# ESP32S2_STICK.net
KiCad netlist of a schematic drawn in EAGLE
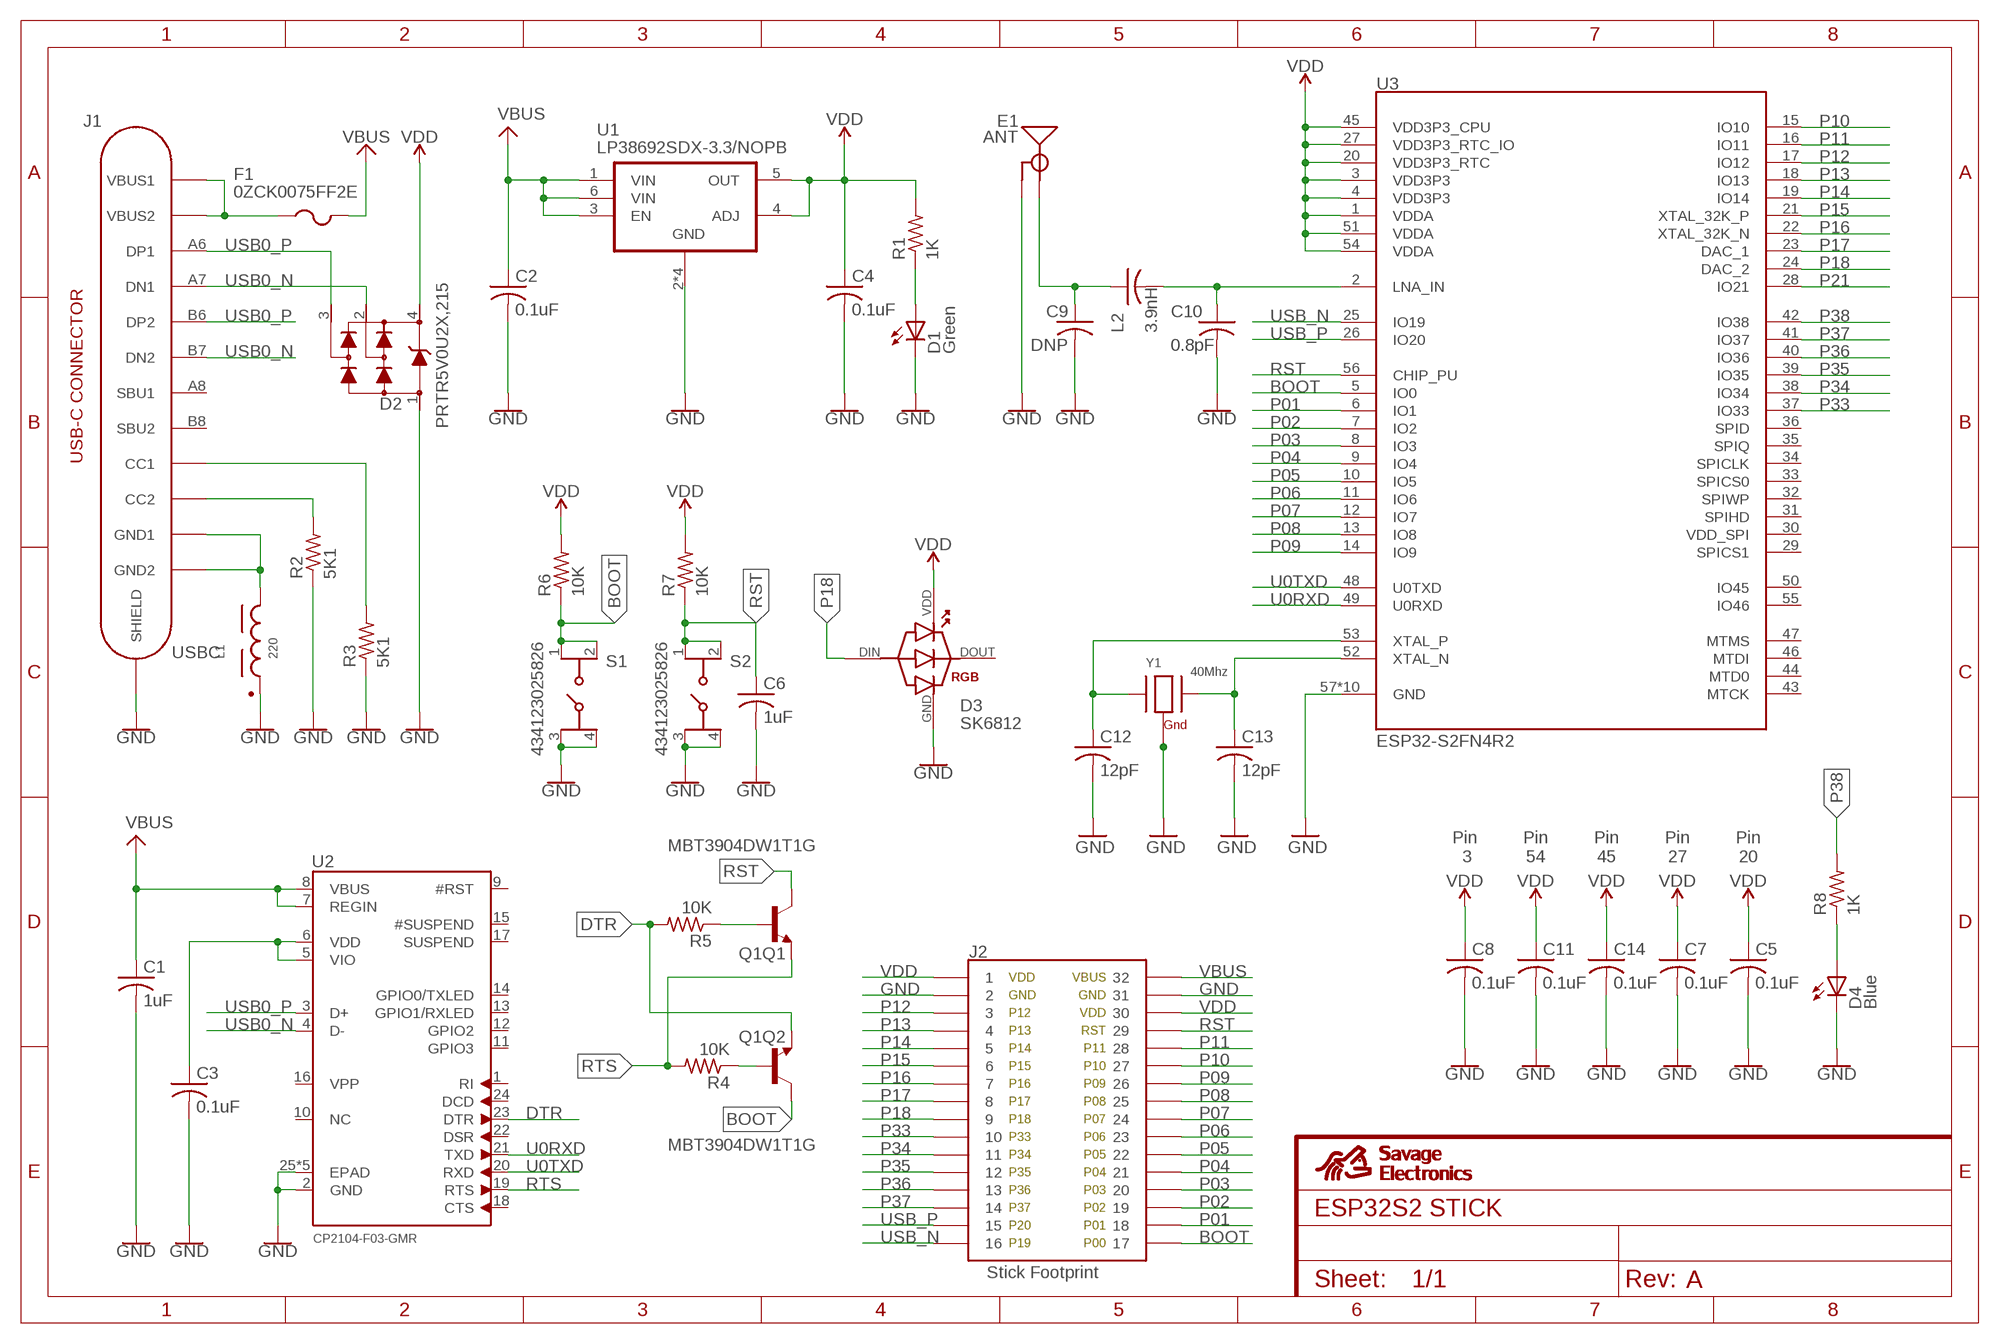
[diagram p0: schematic, sheet 1]

(export (version "E")
  (design (tool "Eeschema 10.0.6"))
  (components
    (comp (ref "C1")
      (value "1uF")
      (footprint "eagle-import:C0603")
      (libsource (lib "eagle-import") (part "adafruit_8559999_C-USC0603"))
    )
    (comp (ref "C2")
      (value "0.1uF")
      (footprint "eagle-import:C0603")
      (libsource (lib "eagle-import") (part "C-USC0603"))
    )
    (comp (ref "C3")
      (value "0.1uF")
      (footprint "eagle-import:C0603")
      (libsource (lib "eagle-import") (part "C-USC0603"))
    )
    (comp (ref "C4")
      (value "0.1uF")
      (footprint "eagle-import:C0603")
      (libsource (lib "eagle-import") (part "C-USC0603"))
    )
    (comp (ref "C5")
      (value "0.1uF")
      (footprint "eagle-import:C0603")
      (libsource (lib "eagle-import") (part "C-USC0603"))
    )
    (comp (ref "C6")
      (value "1uF")
      (footprint "eagle-import:C0603")
      (libsource (lib "eagle-import") (part "C-USC0603"))
    )
    (comp (ref "C7")
      (value "0.1uF")
      (footprint "eagle-import:C0603")
      (libsource (lib "eagle-import") (part "C-USC0603"))
    )
    (comp (ref "C8")
      (value "0.1uF")
      (footprint "eagle-import:C0603")
      (libsource (lib "eagle-import") (part "C-USC0603"))
    )
    (comp (ref "C9")
      (value "DNP")
      (footprint "eagle-import:C0402")
      (libsource (lib "eagle-import") (part "C-USC0402"))
    )
    (comp (ref "C10")
      (value "0.8pF")
      (footprint "eagle-import:C0402")
      (libsource (lib "eagle-import") (part "C-USC0402"))
    )
    (comp (ref "C11")
      (value "0.1uF")
      (footprint "eagle-import:C0603")
      (libsource (lib "eagle-import") (part "C-USC0603"))
    )
    (comp (ref "C12")
      (value "12pF")
      (footprint "eagle-import:C0402")
      (libsource (lib "eagle-import") (part "C-USC0402"))
    )
    (comp (ref "C13")
      (value "12pF")
      (footprint "eagle-import:C0402")
      (libsource (lib "eagle-import") (part "C-USC0402"))
    )
    (comp (ref "C14")
      (value "0.1uF")
      (footprint "eagle-import:C0603")
      (libsource (lib "eagle-import") (part "C-USC0603"))
    )
    (comp (ref "D1")
      (value "Green")
      (footprint "eagle-import:CHIP-LED0603")
      (libsource (lib "eagle-import") (part "LEDCHIP-LED0603"))
    )
    (comp (ref "D2")
      (value "PRTR5V0U2X,215")
      (footprint "eagle-import:SOT143B")
      (libsource (lib "eagle-import") (part "PRTR5V0U2X,215"))
    )
    (comp (ref "D3")
      (value "SK6812")
      (footprint "eagle-import:20X20")
      (libsource (lib "eagle-import") (part "SK6812"))
    )
    (comp (ref "D4")
      (value "Blue")
      (footprint "eagle-import:CHIP-LED0603")
      (libsource (lib "eagle-import") (part "LEDCHIP-LED0603"))
    )
    (comp (ref "E1")
      (value "ANT")
      (footprint "eagle-import:TRACE_ANTENNA_2.4GHZ_15.2MM")
      (libsource (lib "eagle-import") (part "ANTENNA-GROUNDEDTRACE-15.2MM"))
    )
    (comp (ref "F1")
      (value "0ZCK0075FF2E")
      (footprint "eagle-import:R0603F")
      (libsource (lib "eagle-import") (part "PTCFUSE"))
    )
    (comp (ref "J1")
      (value "USBC")
      (footprint "eagle-import:USBC")
      (libsource (lib "eagle-import") (part "USBC"))
    )
    (comp (ref "J2")
      (value "Stick Footprint")
      (footprint "eagle-import:NRF52832_CASTELLATED")
      (libsource (lib "eagle-import") (part "NRF52832PRO"))
    )
    (comp (ref "L1")
      (value "220")
      (footprint "eagle-import:WE-CBA_0603(W=2.2)")
      (libsource (lib "eagle-import") (part "WE-CBA_0603_WB/HS_782631182"))
    )
    (comp (ref "L2")
      (value "3.9nH")
      (footprint "eagle-import:C0402")
      (libsource (lib "eagle-import") (part "C-USC0402"))
    )
    (comp (ref "Q1")
      (value "MBT3904DW1T1G")
      (footprint "eagle-import:SC70-6")
      (libsource (lib "eagle-import") (part "TRANS_NPN_DUAL-MBT3904DW1T1"))
    )
    (comp (ref "R1")
      (value "1K")
      (footprint "eagle-import:R0402")
      (libsource (lib "eagle-import") (part "R-US_R0402"))
    )
    (comp (ref "R2")
      (value "5K1")
      (footprint "eagle-import:R0402")
      (libsource (lib "eagle-import") (part "R-US_R0402"))
    )
    (comp (ref "R3")
      (value "5K1")
      (footprint "eagle-import:R0402")
      (libsource (lib "eagle-import") (part "R-US_R0402"))
    )
    (comp (ref "R4")
      (value "10K")
      (footprint "eagle-import:R0402")
      (libsource (lib "eagle-import") (part "R-US_R0402"))
    )
    (comp (ref "R5")
      (value "10K")
      (footprint "eagle-import:R0402")
      (libsource (lib "eagle-import") (part "R-US_R0402"))
    )
    (comp (ref "R6")
      (value "10K")
      (footprint "eagle-import:R0402")
      (libsource (lib "eagle-import") (part "R-US_R0402"))
    )
    (comp (ref "R7")
      (value "10K")
      (footprint "eagle-import:R0402")
      (libsource (lib "eagle-import") (part "R-US_R0402"))
    )
    (comp (ref "R8")
      (value "1K")
      (footprint "eagle-import:R0402")
      (libsource (lib "eagle-import") (part "R-US_R0402"))
    )
    (comp (ref "S1")
      (value "434123025826")
      (footprint "eagle-import:434123025826")
      (libsource (lib "eagle-import") (part "434123025826"))
    )
    (comp (ref "S2")
      (value "434123025826")
      (footprint "eagle-import:434123025826")
      (libsource (lib "eagle-import") (part "434123025826"))
    )
    (comp (ref "U1")
      (value "LP38692SDX-3.3/NOPB")
      (footprint "eagle-import:LLP6-3X3")
      (fields (field (name "MF") "Texas Instruments"))
      (libsource (lib "eagle-import") (part "LP38692SDX-3.3/NOPB"))
    )
    (comp (ref "U2")
      (value "CP2102N-A02-GQFN24R")
      (footprint "eagle-import:QFN24_4MM_SMSC")
      (libsource (lib "eagle-import") (part "CP2104"))
    )
    (comp (ref "U3")
      (value "ESP32-S2FN4R2")
      (footprint "eagle-import:QFN40P700X700X90-57T400N")
      (libsource (lib "eagle-import") (part "ESP32-S2QFN54"))
    )
    (comp (ref "Y1")
      (value "40Mhz")
      (footprint "eagle-import:NX2016")
      (libsource (lib "eagle-import") (part "XTAL-4"))
    )
  )
  (nets
    (net (code "1") (name "/P01") (class "Default")
      (node (ref "J2") (pin "16") (pinfunction "18_16") (pintype "bidirectional"))
      (node (ref "J2") (pin "16B") (pinfunction "18_16B") (pintype "bidirectional"))
      (node (ref "J2") (pin "16C") (pinfunction "18_16C") (pintype "bidirectional"))
      (node (ref "J2") (pin "P16") (pinfunction "18_P16") (pintype "bidirectional"))
      (node (ref "U3") (pin "6") (pinfunction "IO1_6") (pintype "bidirectional"))
    )
    (net (code "2") (name "/P02") (class "Default")
      (node (ref "J2") (pin "17") (pinfunction "19_17") (pintype "bidirectional"))
      (node (ref "J2") (pin "17B") (pinfunction "19_17B") (pintype "bidirectional"))
      (node (ref "J2") (pin "17C") (pinfunction "19_17C") (pintype "bidirectional"))
      (node (ref "J2") (pin "P17") (pinfunction "19_P17") (pintype "bidirectional"))
      (node (ref "U3") (pin "7") (pinfunction "IO2_7") (pintype "bidirectional"))
    )
    (net (code "3") (name "/P03") (class "Default")
      (node (ref "J2") (pin "18") (pinfunction "20_18") (pintype "bidirectional"))
      (node (ref "J2") (pin "18B") (pinfunction "20_18B") (pintype "bidirectional"))
      (node (ref "J2") (pin "18C") (pinfunction "20_18C") (pintype "bidirectional"))
      (node (ref "J2") (pin "P18") (pinfunction "20_P18") (pintype "bidirectional"))
      (node (ref "U3") (pin "8") (pinfunction "IO3_8") (pintype "bidirectional"))
    )
    (net (code "4") (name "/P04") (class "Default")
      (node (ref "J2") (pin "19") (pinfunction "21_19") (pintype "bidirectional"))
      (node (ref "J2") (pin "19B") (pinfunction "21_19B") (pintype "bidirectional"))
      (node (ref "J2") (pin "19C") (pinfunction "21_19C") (pintype "bidirectional"))
      (node (ref "J2") (pin "P19") (pinfunction "21_P19") (pintype "bidirectional"))
      (node (ref "U3") (pin "9") (pinfunction "IO4_9") (pintype "bidirectional"))
    )
    (net (code "5") (name "/P05") (class "Default")
      (node (ref "J2") (pin "20") (pinfunction "22_20") (pintype "bidirectional"))
      (node (ref "J2") (pin "20B") (pinfunction "22_20B") (pintype "bidirectional"))
      (node (ref "J2") (pin "20C") (pinfunction "22_20C") (pintype "bidirectional"))
      (node (ref "J2") (pin "P20") (pinfunction "22_P20") (pintype "bidirectional"))
      (node (ref "U3") (pin "10") (pinfunction "IO5_10") (pintype "bidirectional"))
    )
    (net (code "6") (name "/P06") (class "Default")
      (node (ref "J2") (pin "21") (pinfunction "23_21") (pintype "bidirectional"))
      (node (ref "J2") (pin "21B") (pinfunction "23_21B") (pintype "bidirectional"))
      (node (ref "J2") (pin "21C") (pinfunction "23_21C") (pintype "bidirectional"))
      (node (ref "J2") (pin "P21") (pinfunction "23_P21") (pintype "bidirectional"))
      (node (ref "U3") (pin "11") (pinfunction "IO6_11") (pintype "bidirectional"))
    )
    (net (code "7") (name "/P07") (class "Default")
      (node (ref "J2") (pin "22") (pinfunction "24_22") (pintype "bidirectional"))
      (node (ref "J2") (pin "22B") (pinfunction "24_22B") (pintype "bidirectional"))
      (node (ref "J2") (pin "22C") (pinfunction "24_22C") (pintype "bidirectional"))
      (node (ref "J2") (pin "P22") (pinfunction "24_P22") (pintype "bidirectional"))
      (node (ref "U3") (pin "12") (pinfunction "IO7_12") (pintype "bidirectional"))
    )
    (net (code "8") (name "/P08") (class "Default")
      (node (ref "J2") (pin "23") (pinfunction "25_23") (pintype "bidirectional"))
      (node (ref "J2") (pin "23B") (pinfunction "25_23B") (pintype "bidirectional"))
      (node (ref "J2") (pin "23C") (pinfunction "25_23C") (pintype "bidirectional"))
      (node (ref "J2") (pin "P23") (pinfunction "25_P23") (pintype "bidirectional"))
      (node (ref "U3") (pin "13") (pinfunction "IO8_13") (pintype "bidirectional"))
    )
    (net (code "9") (name "/P09") (class "Default")
      (node (ref "J2") (pin "24") (pinfunction "26_24") (pintype "bidirectional"))
      (node (ref "J2") (pin "24B") (pinfunction "26_24B") (pintype "bidirectional"))
      (node (ref "J2") (pin "24C") (pinfunction "26_24C") (pintype "bidirectional"))
      (node (ref "J2") (pin "P24") (pinfunction "26_P24") (pintype "bidirectional"))
      (node (ref "U3") (pin "14") (pinfunction "IO9_14") (pintype "bidirectional"))
    )
    (net (code "10") (name "/P10") (class "Default")
      (node (ref "J2") (pin "25") (pinfunction "27_25") (pintype "bidirectional"))
      (node (ref "J2") (pin "25B") (pinfunction "27_25B") (pintype "bidirectional"))
      (node (ref "J2") (pin "25C") (pinfunction "27_25C") (pintype "bidirectional"))
      (node (ref "J2") (pin "P25") (pinfunction "27_P25") (pintype "bidirectional"))
      (node (ref "U3") (pin "15") (pinfunction "IO10_15") (pintype "bidirectional"))
    )
    (net (code "11") (name "/P11") (class "Default")
      (node (ref "J2") (pin "26") (pinfunction "28_26") (pintype "bidirectional"))
      (node (ref "J2") (pin "26B") (pinfunction "28_26B") (pintype "bidirectional"))
      (node (ref "J2") (pin "26C") (pinfunction "28_26C") (pintype "bidirectional"))
      (node (ref "J2") (pin "P26") (pinfunction "28_P26") (pintype "bidirectional"))
      (node (ref "U3") (pin "16") (pinfunction "IO11_16") (pintype "bidirectional"))
    )
    (net (code "12") (name "/P12") (class "Default")
      (node (ref "J2") (pin "3") (pinfunction "3_3") (pintype "bidirectional"))
      (node (ref "J2") (pin "3B") (pinfunction "3_3B") (pintype "bidirectional"))
      (node (ref "J2") (pin "3C") (pinfunction "3_3C") (pintype "bidirectional"))
      (node (ref "J2") (pin "P3") (pinfunction "3_P3") (pintype "bidirectional"))
      (node (ref "U3") (pin "17") (pinfunction "IO12_17") (pintype "bidirectional"))
    )
    (net (code "13") (name "/P13") (class "Default")
      (node (ref "J2") (pin "4") (pinfunction "4_4") (pintype "bidirectional"))
      (node (ref "J2") (pin "4B") (pinfunction "4_4B") (pintype "bidirectional"))
      (node (ref "J2") (pin "4C") (pinfunction "4_4C") (pintype "bidirectional"))
      (node (ref "J2") (pin "P4") (pinfunction "4_P4") (pintype "bidirectional"))
      (node (ref "U3") (pin "18") (pinfunction "IO13_18") (pintype "bidirectional"))
    )
    (net (code "14") (name "/P14") (class "Default")
      (node (ref "J2") (pin "5") (pinfunction "5_5") (pintype "bidirectional"))
      (node (ref "J2") (pin "5B") (pinfunction "5_5B") (pintype "bidirectional"))
      (node (ref "J2") (pin "5C") (pinfunction "5_5C") (pintype "bidirectional"))
      (node (ref "J2") (pin "P5") (pinfunction "5_P5") (pintype "bidirectional"))
      (node (ref "U3") (pin "19") (pinfunction "IO14_19") (pintype "bidirectional"))
    )
    (net (code "15") (name "/P15") (class "Default")
      (node (ref "J2") (pin "6") (pinfunction "6_6") (pintype "bidirectional"))
      (node (ref "J2") (pin "6B") (pinfunction "6_6B") (pintype "bidirectional"))
      (node (ref "J2") (pin "6C") (pinfunction "6_6C") (pintype "bidirectional"))
      (node (ref "J2") (pin "P6") (pinfunction "6_P6") (pintype "bidirectional"))
      (node (ref "U3") (pin "21") (pinfunction "XTAL_32K_P_21") (pintype "bidirectional"))
    )
    (net (code "16") (name "/P16") (class "Default")
      (node (ref "J2") (pin "7") (pinfunction "7_7") (pintype "bidirectional"))
      (node (ref "J2") (pin "7B") (pinfunction "7_7B") (pintype "bidirectional"))
      (node (ref "J2") (pin "7C") (pinfunction "7_7C") (pintype "bidirectional"))
      (node (ref "J2") (pin "P7") (pinfunction "7_P7") (pintype "bidirectional"))
      (node (ref "U3") (pin "22") (pinfunction "XTAL_32K_N_22") (pintype "bidirectional"))
    )
    (net (code "17") (name "/P17") (class "Default")
      (node (ref "J2") (pin "8") (pinfunction "8_8") (pintype "bidirectional"))
      (node (ref "J2") (pin "8B") (pinfunction "8_8B") (pintype "bidirectional"))
      (node (ref "J2") (pin "8C") (pinfunction "8_8C") (pintype "bidirectional"))
      (node (ref "J2") (pin "P8") (pinfunction "8_P8") (pintype "bidirectional"))
      (node (ref "U3") (pin "23") (pinfunction "DAC_1_23") (pintype "bidirectional"))
    )
    (net (code "18") (name "/P21") (class "Default")
      (node (ref "U3") (pin "28") (pinfunction "IO21_28") (pintype "bidirectional"))
    )
    (net (code "19") (name "/P33") (class "Default")
      (node (ref "J2") (pin "10") (pinfunction "10_10") (pintype "bidirectional"))
      (node (ref "J2") (pin "10B") (pinfunction "10_10B") (pintype "bidirectional"))
      (node (ref "J2") (pin "10C") (pinfunction "10_10C") (pintype "bidirectional"))
      (node (ref "J2") (pin "P10") (pinfunction "10_P10") (pintype "bidirectional"))
      (node (ref "U3") (pin "37") (pinfunction "IO33_37") (pintype "bidirectional"))
    )
    (net (code "20") (name "/P34") (class "Default")
      (node (ref "J2") (pin "11") (pinfunction "11_11") (pintype "bidirectional"))
      (node (ref "J2") (pin "11B") (pinfunction "11_11B") (pintype "bidirectional"))
      (node (ref "J2") (pin "11C") (pinfunction "11_11C") (pintype "bidirectional"))
      (node (ref "J2") (pin "P11") (pinfunction "11_P11") (pintype "bidirectional"))
      (node (ref "U3") (pin "38") (pinfunction "IO34_38") (pintype "bidirectional"))
    )
    (net (code "21") (name "/P35") (class "Default")
      (node (ref "J2") (pin "12") (pinfunction "12_12") (pintype "bidirectional"))
      (node (ref "J2") (pin "12B") (pinfunction "12_12B") (pintype "bidirectional"))
      (node (ref "J2") (pin "12C") (pinfunction "12_12C") (pintype "bidirectional"))
      (node (ref "J2") (pin "P12") (pinfunction "12_P12") (pintype "bidirectional"))
      (node (ref "U3") (pin "39") (pinfunction "IO35_39") (pintype "bidirectional"))
    )
    (net (code "22") (name "/P36") (class "Default")
      (node (ref "J2") (pin "13") (pinfunction "13_13") (pintype "bidirectional"))
      (node (ref "J2") (pin "13B") (pinfunction "13_13B") (pintype "bidirectional"))
      (node (ref "J2") (pin "13C") (pinfunction "13_13C") (pintype "bidirectional"))
      (node (ref "J2") (pin "P13") (pinfunction "13_P13") (pintype "bidirectional"))
      (node (ref "U3") (pin "40") (pinfunction "IO36_40") (pintype "bidirectional"))
    )
    (net (code "23") (name "/P37") (class "Default")
      (node (ref "J2") (pin "14") (pinfunction "14_14") (pintype "bidirectional"))
      (node (ref "J2") (pin "14B") (pinfunction "14_14B") (pintype "bidirectional"))
      (node (ref "J2") (pin "14C") (pinfunction "14_14C") (pintype "bidirectional"))
      (node (ref "J2") (pin "P14") (pinfunction "14_P14") (pintype "bidirectional"))
      (node (ref "U3") (pin "41") (pinfunction "IO37_41") (pintype "bidirectional"))
    )
    (net (code "24") (name "/U0RXD") (class "Default")
      (node (ref "U2") (pin "21") (pinfunction "TXD_21") (pintype "output"))
      (node (ref "U3") (pin "49") (pinfunction "U0RXD_49") (pintype "bidirectional"))
    )
    (net (code "25") (name "/U0TXD") (class "Default")
      (node (ref "U2") (pin "20") (pinfunction "RXD_20") (pintype "input"))
      (node (ref "U3") (pin "48") (pinfunction "U0TXD_48") (pintype "bidirectional"))
    )
    (net (code "26") (name "/USB0_N") (class "Default")
      (node (ref "D2") (pin "2") (pinfunction "P$2_2") (pintype "passive"))
      (node (ref "J1") (pin "A7") (pinfunction "DN1_A7") (pintype "bidirectional"))
      (node (ref "J1") (pin "B7") (pinfunction "DN2_B7") (pintype "bidirectional"))
      (node (ref "U2") (pin "4") (pinfunction "D-_4") (pintype "bidirectional"))
    )
    (net (code "27") (name "/USB0_P") (class "Default")
      (node (ref "D2") (pin "3") (pinfunction "P$3_3") (pintype "passive"))
      (node (ref "J1") (pin "A6") (pinfunction "DP1_A6") (pintype "bidirectional"))
      (node (ref "J1") (pin "B6") (pinfunction "DP2_B6") (pintype "bidirectional"))
      (node (ref "U2") (pin "3") (pinfunction "D+_3") (pintype "bidirectional"))
    )
    (net (code "28") (name "/USB_N") (class "Default")
      (node (ref "J2") (pin "16AA") (pinfunction "16_16AA") (pintype "bidirectional"))
      (node (ref "J2") (pin "16BB") (pinfunction "16_16BB") (pintype "bidirectional"))
      (node (ref "J2") (pin "16CC") (pinfunction "16_16CC") (pintype "bidirectional"))
      (node (ref "J2") (pin "P16A") (pinfunction "16_P16A") (pintype "bidirectional"))
      (node (ref "U3") (pin "25") (pinfunction "IO19_25") (pintype "bidirectional"))
    )
    (net (code "29") (name "/USB_P") (class "Default")
      (node (ref "J2") (pin "15") (pinfunction "15_15") (pintype "bidirectional"))
      (node (ref "J2") (pin "15B") (pinfunction "15_15B") (pintype "bidirectional"))
      (node (ref "J2") (pin "15C") (pinfunction "15_15C") (pintype "bidirectional"))
      (node (ref "J2") (pin "P15") (pinfunction "15_P15") (pintype "bidirectional"))
      (node (ref "U3") (pin "26") (pinfunction "IO20_26") (pintype "bidirectional"))
    )
    (net (code "30") (name "/VDD_SPI") (class "Default")
      (node (ref "U3") (pin "30") (pinfunction "VDD_SPI_30") (pintype "power_in"))
    )
    (net (code "31") (name "BOOT") (class "Default")
      (node (ref "J2") (pin "17AA") (pinfunction "17_17AA") (pintype "bidirectional"))
      (node (ref "J2") (pin "17BB") (pinfunction "17_17BB") (pintype "bidirectional"))
      (node (ref "J2") (pin "17CC") (pinfunction "17_17CC") (pintype "bidirectional"))
      (node (ref "J2") (pin "P17DD") (pinfunction "17_P17DD") (pintype "bidirectional"))
      (node (ref "Q1") (pin "6") (pinfunction "C_6") (pintype "passive"))
      (node (ref "R6") (pin "1") (pinfunction "1_1") (pintype "passive"))
      (node (ref "S1") (pin "1") (pinfunction "1_1") (pintype "passive"))
      (node (ref "S1") (pin "2") (pinfunction "2_2") (pintype "passive"))
      (node (ref "U3") (pin "5") (pinfunction "IO0_5") (pintype "bidirectional"))
    )
    (net (code "32") (name "DTR") (class "Default")
      (node (ref "Q1") (pin "1") (pinfunction "E_1") (pintype "passive"))
      (node (ref "R5") (pin "2") (pinfunction "2_2") (pintype "passive"))
      (node (ref "U2") (pin "23") (pinfunction "DTR_23") (pintype "output"))
    )
    (net (code "33") (name "GND") (class "Default")
      (node (ref "C1") (pin "2") (pinfunction "2_2") (pintype "passive"))
      (node (ref "C10") (pin "2") (pinfunction "2_2") (pintype "passive"))
      (node (ref "C11") (pin "2") (pinfunction "2_2") (pintype "passive"))
      (node (ref "C12") (pin "2") (pinfunction "2_2") (pintype "passive"))
      (node (ref "C13") (pin "2") (pinfunction "2_2") (pintype "passive"))
      (node (ref "C14") (pin "2") (pinfunction "2_2") (pintype "passive"))
      (node (ref "C2") (pin "2") (pinfunction "2_2") (pintype "passive"))
      (node (ref "C3") (pin "2") (pinfunction "2_2") (pintype "passive"))
      (node (ref "C4") (pin "2") (pinfunction "2_2") (pintype "passive"))
      (node (ref "C5") (pin "2") (pinfunction "2_2") (pintype "passive"))
      (node (ref "C6") (pin "2") (pinfunction "2_2") (pintype "passive"))
      (node (ref "C7") (pin "2") (pinfunction "2_2") (pintype "passive"))
      (node (ref "C8") (pin "2") (pinfunction "2_2") (pintype "passive"))
      (node (ref "C9") (pin "2") (pinfunction "2_2") (pintype "passive"))
      (node (ref "D1") (pin "C") (pinfunction "C_C") (pintype "passive"))
      (node (ref "D2") (pin "1") (pinfunction "P$1_1") (pintype "passive"))
      (node (ref "D3") (pin "3") (pinfunction "GND_3") (pintype "bidirectional"))
      (node (ref "D4") (pin "C") (pinfunction "C_C") (pintype "passive"))
      (node (ref "E1") (pin "GND") (pinfunction "GND_GND") (pintype "bidirectional"))
      (node (ref "J1") (pin "S1") (pinfunction "SHIELD_S1") (pintype "bidirectional"))
      (node (ref "J1") (pin "S2") (pinfunction "SHIELD_S2") (pintype "bidirectional"))
      (node (ref "J1") (pin "S3") (pinfunction "SHIELD_S3") (pintype "bidirectional"))
      (node (ref "J1") (pin "S4") (pinfunction "SHIELD_S4") (pintype "bidirectional"))
      (node (ref "J2") (pin "2") (pinfunction "2_2") (pintype "bidirectional"))
      (node (ref "J2") (pin "29") (pinfunction "31_29") (pintype "bidirectional"))
      (node (ref "J2") (pin "29B") (pinfunction "31_29B") (pintype "bidirectional"))
      (node (ref "J2") (pin "29C") (pinfunction "31_29C") (pintype "bidirectional"))
      (node (ref "J2") (pin "2B") (pinfunction "2_2B") (pintype "bidirectional"))
      (node (ref "J2") (pin "2C") (pinfunction "2_2C") (pintype "bidirectional"))
      (node (ref "J2") (pin "P2") (pinfunction "2_P2") (pintype "bidirectional"))
      (node (ref "J2") (pin "P29") (pinfunction "31_P29") (pintype "bidirectional"))
      (node (ref "L1") (pin "1") (pinfunction "1_1") (pintype "passive"))
      (node (ref "R2") (pin "1") (pinfunction "1_1") (pintype "passive"))
      (node (ref "R3") (pin "1") (pinfunction "1_1") (pintype "passive"))
      (node (ref "S1") (pin "3") (pinfunction "3_3") (pintype "passive"))
      (node (ref "S1") (pin "4") (pinfunction "4_4") (pintype "passive"))
      (node (ref "S2") (pin "3") (pinfunction "3_3") (pintype "passive"))
      (node (ref "S2") (pin "4") (pinfunction "4_4") (pintype "passive"))
      (node (ref "U1") (pin "2") (pinfunction "GND_2") (pintype "power_in"))
      (node (ref "U1") (pin "P$1") (pinfunction "GND_P$1") (pintype "power_in"))
      (node (ref "U1") (pin "P$2") (pinfunction "GND_P$2") (pintype "power_in"))
      (node (ref "U1") (pin "P$3") (pinfunction "GND_P$3") (pintype "power_in"))
      (node (ref "U2") (pin "2") (pinfunction "GND_2") (pintype "power_in"))
      (node (ref "U2") (pin "25") (pinfunction "EPAD_25") (pintype "power_in"))
      (node (ref "U2") (pin "P$1") (pinfunction "EPAD_P$1") (pintype "power_in"))
      (node (ref "U2") (pin "P$2") (pinfunction "EPAD_P$2") (pintype "power_in"))
      (node (ref "U2") (pin "P$3") (pinfunction "EPAD_P$3") (pintype "power_in"))
      (node (ref "U2") (pin "P$4") (pinfunction "EPAD_P$4") (pintype "power_in"))
      (node (ref "U3") (pin "57") (pinfunction "GND_57") (pintype "power_in"))
      (node (ref "U3") (pin "P$1") (pinfunction "GND_P$1") (pintype "power_in"))
      (node (ref "U3") (pin "P$2") (pinfunction "GND_P$2") (pintype "power_in"))
      (node (ref "U3") (pin "P$3") (pinfunction "GND_P$3") (pintype "power_in"))
      (node (ref "U3") (pin "P$4") (pinfunction "GND_P$4") (pintype "power_in"))
      (node (ref "U3") (pin "P$5") (pinfunction "GND_P$5") (pintype "power_in"))
      (node (ref "U3") (pin "P$6") (pinfunction "GND_P$6") (pintype "power_in"))
      (node (ref "U3") (pin "P$7") (pinfunction "GND_P$7") (pintype "power_in"))
      (node (ref "U3") (pin "P$8") (pinfunction "GND_P$8") (pintype "power_in"))
      (node (ref "U3") (pin "P$9") (pinfunction "GND_P$9") (pintype "power_in"))
      (node (ref "Y1") (pin "2") (pinfunction "G2_2") (pintype "power_in"))
      (node (ref "Y1") (pin "4") (pinfunction "G1_4") (pintype "power_in"))
    )
    (net (code "34") (name "Net-(D1-PadA)") (class "Default")
      (node (ref "D1") (pin "A") (pinfunction "A_A") (pintype "passive"))
      (node (ref "R1") (pin "1") (pinfunction "1_1") (pintype "passive"))
    )
    (net (code "35") (name "Net-(D4-PadA)") (class "Default")
      (node (ref "D4") (pin "A") (pinfunction "A_A") (pintype "passive"))
      (node (ref "R8") (pin "1") (pinfunction "1_1") (pintype "passive"))
    )
    (net (code "36") (name "Net-(E1-SIGNAL)") (class "Default")
      (node (ref "C9") (pin "1") (pinfunction "1_1") (pintype "passive"))
      (node (ref "E1") (pin "ANT") (pinfunction "SIGNAL_ANT") (pintype "bidirectional"))
      (node (ref "L2") (pin "1") (pinfunction "1_1") (pintype "passive"))
    )
    (net (code "37") (name "Net-(J1-CC1)") (class "Default")
      (node (ref "J1") (pin "A5") (pinfunction "CC1_A5") (pintype "bidirectional"))
      (node (ref "R3") (pin "2") (pinfunction "2_2") (pintype "passive"))
    )
    (net (code "38") (name "Net-(J1-CC2)") (class "Default")
      (node (ref "J1") (pin "B5") (pinfunction "CC2_B5") (pintype "bidirectional"))
      (node (ref "R2") (pin "2") (pinfunction "2_2") (pintype "passive"))
    )
    (net (code "39") (name "Net-(J1-GND1)") (class "Default")
      (node (ref "J1") (pin "A1B12") (pinfunction "GND1_A1B12") (pintype "bidirectional"))
      (node (ref "J1") (pin "B1A12") (pinfunction "GND2_B1A12") (pintype "bidirectional"))
      (node (ref "L1") (pin "2") (pinfunction "2_2") (pintype "passive"))
    )
    (net (code "40") (name "Net-(J1-VBUS1)") (class "Default")
      (node (ref "F1") (pin "1") (pinfunction "1_1") (pintype "passive"))
      (node (ref "J1") (pin "A4B9") (pinfunction "VBUS1_A4B9") (pintype "bidirectional"))
      (node (ref "J1") (pin "B4A9") (pinfunction "VBUS2_B4A9") (pintype "bidirectional"))
    )
    (net (code "41") (name "Net-(Q1A-B)") (class "Default")
      (node (ref "Q1") (pin "5") (pinfunction "B_5") (pintype "passive"))
      (node (ref "R5") (pin "1") (pinfunction "1_1") (pintype "passive"))
    )
    (net (code "42") (name "Net-(Q1B-B)") (class "Default")
      (node (ref "Q1") (pin "2") (pinfunction "B_2") (pintype "passive"))
      (node (ref "R4") (pin "1") (pinfunction "1_1") (pintype "passive"))
    )
    (net (code "43") (name "Net-(U2-VDD)") (class "Default")
      (node (ref "C3") (pin "1") (pinfunction "1_1") (pintype "passive"))
      (node (ref "U2") (pin "5") (pinfunction "VIO_5") (pintype "power_in"))
      (node (ref "U2") (pin "6") (pinfunction "VDD_6") (pintype "power_in"))
    )
    (net (code "44") (name "Net-(U3-LNA_IN)") (class "Default")
      (node (ref "C10") (pin "1") (pinfunction "1_1") (pintype "passive"))
      (node (ref "L2") (pin "2") (pinfunction "2_2") (pintype "passive"))
      (node (ref "U3") (pin "2") (pinfunction "LNA_IN_2") (pintype "bidirectional"))
    )
    (net (code "45") (name "Net-(U3-XTAL_N)") (class "Default")
      (node (ref "C13") (pin "1") (pinfunction "1_1") (pintype "passive"))
      (node (ref "U3") (pin "52") (pinfunction "XTAL_N_52") (pintype "bidirectional"))
      (node (ref "Y1") (pin "3") (pinfunction "X2_3") (pintype "bidirectional"))
    )
    (net (code "46") (name "Net-(U3-XTAL_P)") (class "Default")
      (node (ref "C12") (pin "1") (pinfunction "1_1") (pintype "passive"))
      (node (ref "U3") (pin "53") (pinfunction "XTAL_P_53") (pintype "bidirectional"))
      (node (ref "Y1") (pin "1") (pinfunction "X1_1") (pintype "bidirectional"))
    )
    (net (code "47") (name "P18") (class "Default")
      (node (ref "D3") (pin "4") (pinfunction "DIN_4") (pintype "bidirectional"))
      (node (ref "J2") (pin "9") (pinfunction "9_9") (pintype "bidirectional"))
      (node (ref "J2") (pin "9B") (pinfunction "9_9B") (pintype "bidirectional"))
      (node (ref "J2") (pin "9C") (pinfunction "9_9C") (pintype "bidirectional"))
      (node (ref "J2") (pin "P9") (pinfunction "9_P9") (pintype "bidirectional"))
      (node (ref "U3") (pin "24") (pinfunction "DAC_2_24") (pintype "bidirectional"))
    )
    (net (code "48") (name "P38") (class "Default")
      (node (ref "R8") (pin "2") (pinfunction "2_2") (pintype "passive"))
      (node (ref "U3") (pin "42") (pinfunction "IO38_42") (pintype "bidirectional"))
    )
    (net (code "49") (name "RST") (class "Default")
      (node (ref "C6") (pin "1") (pinfunction "1_1") (pintype "passive"))
      (node (ref "J2") (pin "27") (pinfunction "29_27") (pintype "bidirectional"))
      (node (ref "J2") (pin "27B") (pinfunction "29_27B") (pintype "bidirectional"))
      (node (ref "J2") (pin "27C") (pinfunction "29_27C") (pintype "bidirectional"))
      (node (ref "J2") (pin "P27") (pinfunction "29_P27") (pintype "bidirectional"))
      (node (ref "Q1") (pin "3") (pinfunction "C_3") (pintype "passive"))
      (node (ref "R7") (pin "1") (pinfunction "1_1") (pintype "passive"))
      (node (ref "S2") (pin "1") (pinfunction "1_1") (pintype "passive"))
      (node (ref "S2") (pin "2") (pinfunction "2_2") (pintype "passive"))
      (node (ref "U3") (pin "56") (pinfunction "CHIP_PU_56") (pintype "input"))
    )
    (net (code "50") (name "RTS") (class "Default")
      (node (ref "Q1") (pin "4") (pinfunction "E_4") (pintype "passive"))
      (node (ref "R4") (pin "2") (pinfunction "2_2") (pintype "passive"))
      (node (ref "U2") (pin "19") (pinfunction "RTS_19") (pintype "output"))
    )
    (net (code "51") (name "VBUS") (class "Default")
      (node (ref "C1") (pin "1") (pinfunction "1_1") (pintype "passive"))
      (node (ref "C2") (pin "1") (pinfunction "1_1") (pintype "passive"))
      (node (ref "F1") (pin "2") (pinfunction "2_2") (pintype "passive"))
      (node (ref "J2") (pin "30") (pinfunction "32_30") (pintype "bidirectional"))
      (node (ref "J2") (pin "30B") (pinfunction "32_30B") (pintype "bidirectional"))
      (node (ref "J2") (pin "30C") (pinfunction "32_30C") (pintype "bidirectional"))
      (node (ref "J2") (pin "P30") (pinfunction "32_P30") (pintype "bidirectional"))
      (node (ref "U1") (pin "1") (pinfunction "VIN_1") (pintype "input"))
      (node (ref "U1") (pin "3") (pinfunction "EN_3") (pintype "input"))
      (node (ref "U1") (pin "6") (pinfunction "VIN_6") (pintype "input"))
      (node (ref "U2") (pin "7") (pinfunction "REGIN_7") (pintype "power_in"))
      (node (ref "U2") (pin "8") (pinfunction "VBUS_8") (pintype "power_in"))
    )
    (net (code "52") (name "VDD") (class "Default")
      (node (ref "C11") (pin "1") (pinfunction "1_1") (pintype "passive"))
      (node (ref "C14") (pin "1") (pinfunction "1_1") (pintype "passive"))
      (node (ref "C4") (pin "1") (pinfunction "1_1") (pintype "passive"))
      (node (ref "C5") (pin "1") (pinfunction "1_1") (pintype "passive"))
      (node (ref "C7") (pin "1") (pinfunction "1_1") (pintype "passive"))
      (node (ref "C8") (pin "1") (pinfunction "1_1") (pintype "passive"))
      (node (ref "D2") (pin "4") (pinfunction "P$4_4") (pintype "passive"))
      (node (ref "D3") (pin "1") (pinfunction "VDD_1") (pintype "bidirectional"))
      (node (ref "J2") (pin "1") (pinfunction "1_1") (pintype "bidirectional"))
      (node (ref "J2") (pin "1B") (pinfunction "1_1B") (pintype "bidirectional"))
      (node (ref "J2") (pin "1C") (pinfunction "1_1C") (pintype "bidirectional"))
      (node (ref "J2") (pin "28") (pinfunction "30_28") (pintype "bidirectional"))
      (node (ref "J2") (pin "28B") (pinfunction "30_28B") (pintype "bidirectional"))
      (node (ref "J2") (pin "28C") (pinfunction "30_28C") (pintype "bidirectional"))
      (node (ref "J2") (pin "P1") (pinfunction "1_P1") (pintype "bidirectional"))
      (node (ref "J2") (pin "P28") (pinfunction "30_P28") (pintype "bidirectional"))
      (node (ref "R1") (pin "2") (pinfunction "2_2") (pintype "passive"))
      (node (ref "R6") (pin "2") (pinfunction "2_2") (pintype "passive"))
      (node (ref "R7") (pin "2") (pinfunction "2_2") (pintype "passive"))
      (node (ref "U1") (pin "4") (pinfunction "ADJ_4") (pintype "input"))
      (node (ref "U1") (pin "5") (pinfunction "OUT_5") (pintype "passive"))
      (node (ref "U3") (pin "1") (pinfunction "VDDA_1") (pintype "power_in"))
      (node (ref "U3") (pin "20") (pinfunction "VDD3P3_RTC_20") (pintype "power_in"))
      (node (ref "U3") (pin "27") (pinfunction "VDD3P3_RTC_IO_27") (pintype "power_in"))
      (node (ref "U3") (pin "3") (pinfunction "VDD3P3_3") (pintype "power_in"))
      (node (ref "U3") (pin "4") (pinfunction "VDD3P3_4") (pintype "power_in"))
      (node (ref "U3") (pin "45") (pinfunction "VDD3P3_CPU_45") (pintype "power_in"))
      (node (ref "U3") (pin "51") (pinfunction "VDDA_51") (pintype "power_in"))
      (node (ref "U3") (pin "54") (pinfunction "VDDA_54") (pintype "power_in"))
    )
    (net (code "53") (name "unconnected-(D3-DOUT-Pad2)") (class "Default")
      (node (ref "D3") (pin "2") (pinfunction "DOUT_2") (pintype "bidirectional"))
    )
    (net (code "54") (name "unconnected-(J1-SBU1-PadA8)") (class "Default")
      (node (ref "J1") (pin "A8") (pinfunction "SBU1_A8") (pintype "bidirectional"))
    )
    (net (code "55") (name "unconnected-(J1-SBU2-PadB8)") (class "Default")
      (node (ref "J1") (pin "B8") (pinfunction "SBU2_B8") (pintype "bidirectional"))
    )
    (net (code "56") (name "unconnected-(U2-#RST-Pad9)") (class "Default")
      (node (ref "U2") (pin "9") (pinfunction "#RST_9") (pintype "bidirectional"))
    )
    (net (code "57") (name "unconnected-(U2-#SUSPEND-Pad15)") (class "Default")
      (node (ref "U2") (pin "15") (pinfunction "#SUSPEND_15") (pintype "output"))
    )
    (net (code "58") (name "unconnected-(U2-CTS-Pad18)") (class "Default")
      (node (ref "U2") (pin "18") (pinfunction "CTS_18") (pintype "input"))
    )
    (net (code "59") (name "unconnected-(U2-DCD-Pad24)") (class "Default")
      (node (ref "U2") (pin "24") (pinfunction "DCD_24") (pintype "input"))
    )
    (net (code "60") (name "unconnected-(U2-DSR-Pad22)") (class "Default")
      (node (ref "U2") (pin "22") (pinfunction "DSR_22") (pintype "input"))
    )
    (net (code "61") (name "unconnected-(U2-GPIO0{slash}TXLED-Pad14)") (class "Default")
      (node (ref "U2") (pin "14") (pinfunction "GPIO0/TXLED_14") (pintype "bidirectional"))
    )
    (net (code "62") (name "unconnected-(U2-GPIO1{slash}RXLED-Pad13)") (class "Default")
      (node (ref "U2") (pin "13") (pinfunction "GPIO1/RXLED_13") (pintype "bidirectional"))
    )
    (net (code "63") (name "unconnected-(U2-GPIO2-Pad12)") (class "Default")
      (node (ref "U2") (pin "12") (pinfunction "GPIO2_12") (pintype "bidirectional"))
    )
    (net (code "64") (name "unconnected-(U2-GPIO3-Pad11)") (class "Default")
      (node (ref "U2") (pin "11") (pinfunction "GPIO3_11") (pintype "bidirectional"))
    )
    (net (code "65") (name "unconnected-(U2-NC-Pad10)") (class "Default")
      (node (ref "U2") (pin "10") (pinfunction "NC_10") (pintype "no_connect"))
    )
    (net (code "66") (name "unconnected-(U2-RI-Pad1)") (class "Default")
      (node (ref "U2") (pin "1") (pinfunction "RI_1") (pintype "input"))
    )
    (net (code "67") (name "unconnected-(U2-SUSPEND-Pad17)") (class "Default")
      (node (ref "U2") (pin "17") (pinfunction "SUSPEND_17") (pintype "output"))
    )
    (net (code "68") (name "unconnected-(U2-VPP-Pad16)") (class "Default")
      (node (ref "U2") (pin "16") (pinfunction "VPP_16") (pintype "bidirectional"))
    )
    (net (code "69") (name "unconnected-(U3-IO45-Pad50)") (class "Default")
      (node (ref "U3") (pin "50") (pinfunction "IO45_50") (pintype "bidirectional"))
    )
    (net (code "70") (name "unconnected-(U3-IO46-Pad55)") (class "Default")
      (node (ref "U3") (pin "55") (pinfunction "IO46_55") (pintype "input"))
    )
    (net (code "71") (name "unconnected-(U3-MTCK-Pad43)") (class "Default")
      (node (ref "U3") (pin "43") (pinfunction "MTCK_43") (pintype "bidirectional"))
    )
    (net (code "72") (name "unconnected-(U3-MTD0-Pad44)") (class "Default")
      (node (ref "U3") (pin "44") (pinfunction "MTD0_44") (pintype "bidirectional"))
    )
    (net (code "73") (name "unconnected-(U3-MTDI-Pad46)") (class "Default")
      (node (ref "U3") (pin "46") (pinfunction "MTDI_46") (pintype "bidirectional"))
    )
    (net (code "74") (name "unconnected-(U3-MTMS-Pad47)") (class "Default")
      (node (ref "U3") (pin "47") (pinfunction "MTMS_47") (pintype "bidirectional"))
    )
    (net (code "75") (name "unconnected-(U3-SPICLK-Pad34)") (class "Default")
      (node (ref "U3") (pin "34") (pinfunction "SPICLK_34") (pintype "bidirectional"))
    )
    (net (code "76") (name "unconnected-(U3-SPICS0-Pad33)") (class "Default")
      (node (ref "U3") (pin "33") (pinfunction "SPICS0_33") (pintype "bidirectional"))
    )
    (net (code "77") (name "unconnected-(U3-SPICS1-Pad29)") (class "Default")
      (node (ref "U3") (pin "29") (pinfunction "SPICS1_29") (pintype "bidirectional"))
    )
    (net (code "78") (name "unconnected-(U3-SPID-Pad36)") (class "Default")
      (node (ref "U3") (pin "36") (pinfunction "SPID_36") (pintype "bidirectional"))
    )
    (net (code "79") (name "unconnected-(U3-SPIHD-Pad31)") (class "Default")
      (node (ref "U3") (pin "31") (pinfunction "SPIHD_31") (pintype "bidirectional"))
    )
    (net (code "80") (name "unconnected-(U3-SPIQ-Pad35)") (class "Default")
      (node (ref "U3") (pin "35") (pinfunction "SPIQ_35") (pintype "bidirectional"))
    )
    (net (code "81") (name "unconnected-(U3-SPIWP-Pad32)") (class "Default")
      (node (ref "U3") (pin "32") (pinfunction "SPIWP_32") (pintype "bidirectional"))
    )
  )
)
